# STM32H7_Expand.net
KiCad netlist of a schematic drawn in Altium Designer
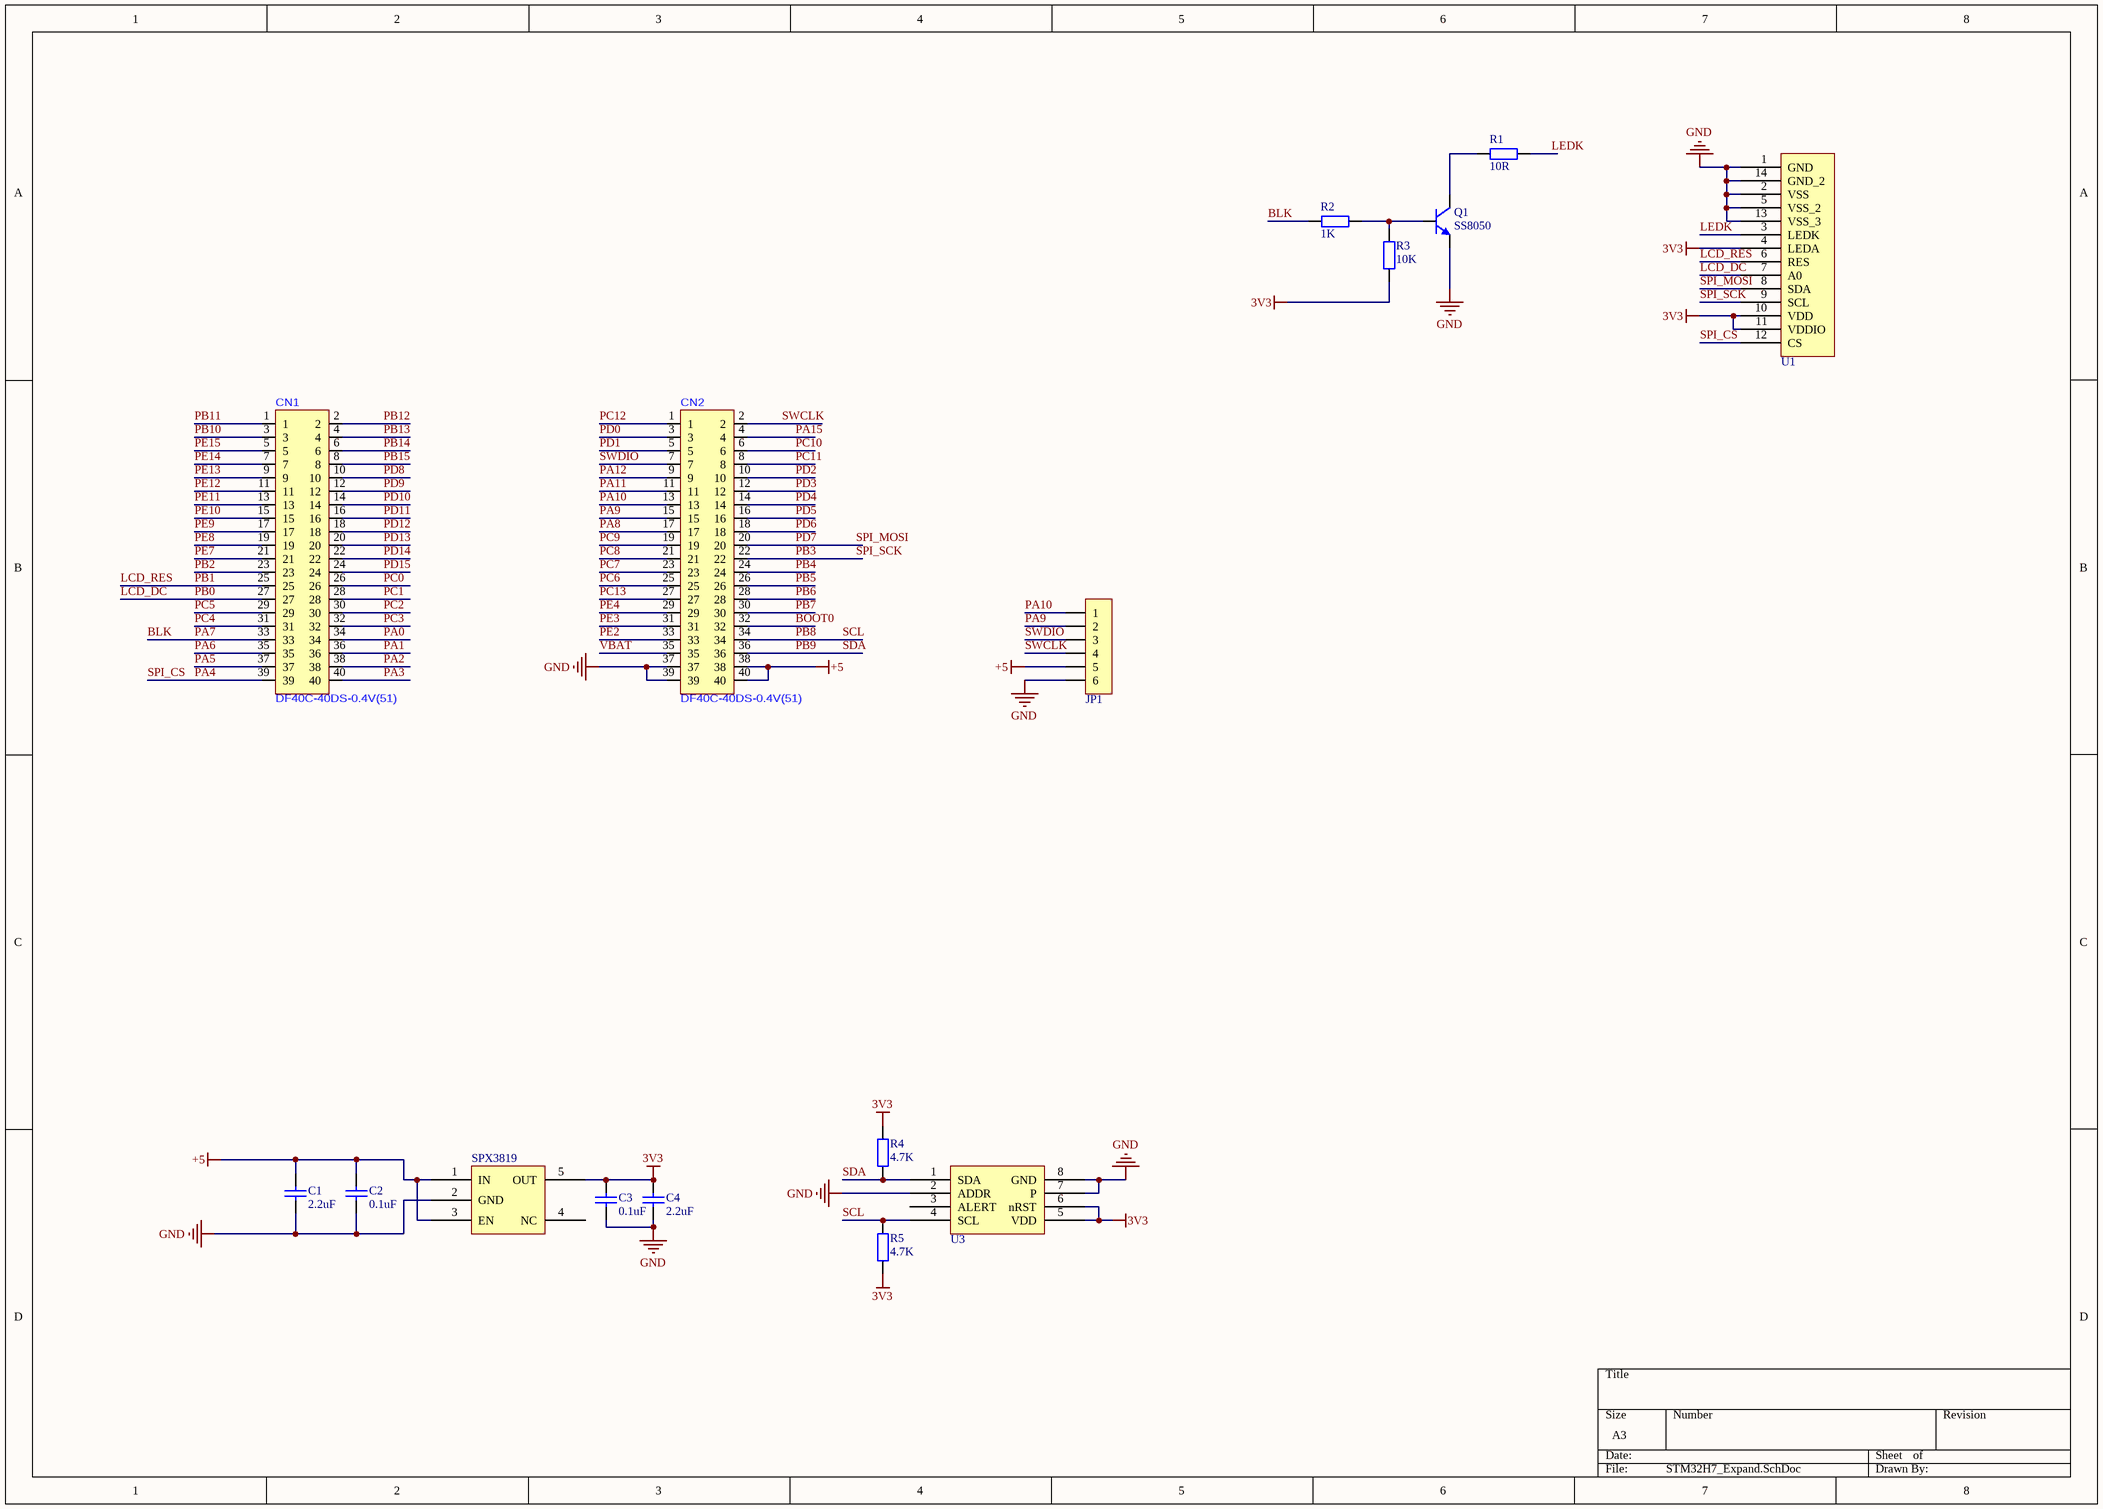
[diagram p0: STM32H7_Expand.SchDoc]

(export (version "E")
  (design (tool "Eeschema 10.0.6"))
  (components
    (comp (ref "C1")
      (value "2.2uF")
      (footprint "C0603_L")
      (description "贴片电容")
      (libsource (lib "0.1 - 电阻-电容-电感-电位器") (part "C"))
    )
    (comp (ref "C2")
      (value "0.1uF")
      (footprint "C0603_L")
      (description "贴片电容")
      (libsource (lib "0.1 - 电阻-电容-电感-电位器") (part "C"))
    )
    (comp (ref "C3")
      (value "0.1uF")
      (footprint "C0603_L")
      (description "贴片电容")
      (libsource (lib "0.1 - 电阻-电容-电感-电位器") (part "C"))
    )
    (comp (ref "C4")
      (value "2.2uF")
      (footprint "C0603_L")
      (description "贴片电容")
      (libsource (lib "0.1 - 电阻-电容-电感-电位器") (part "C"))
    )
    (comp (ref "CN1")
      (value "DF40C-40DS-0.4V(51)")
      (footprint "DF40C-40DS-0.4V")
      (description "BTB 母座\r\nC424644")
      (libsource (lib "Pi") (part "DF40C-40DS-0.4V(51)"))
    )
    (comp (ref "CN2")
      (value "DF40C-40DS-0.4V(51)")
      (footprint "DF40C-40DS-0.4V")
      (description "BTB 母座\r\nC424644")
      (libsource (lib "Pi") (part "DF40C-40DS-0.4V(51)"))
    )
    (comp (ref "JP1")
      (value "HDR-1X6")
      (footprint "ZH1.5-WS-6P")
      (description "6P接插件")
      (libsource (lib "5.2 - 接插件-脚距1.5") (part "Header 6"))
    )
    (comp (ref "Q1")
      (value "SS8050")
      (footprint "SOT23-3N")
      (description "C2150 \r\nNPN")
      (libsource (lib "0.4 - 三极管-场效应管-可控硅") (part "8050-SMD"))
    )
    (comp (ref "R1")
      (value "10R")
      (footprint "R0603_L")
      (description "贴片电阻")
      (libsource (lib "0.1 - 电阻-电容-电感-电位器") (part "R"))
    )
    (comp (ref "R2")
      (value "1K")
      (footprint "R0603_L")
      (description "贴片电阻")
      (libsource (lib "0.1 - 电阻-电容-电感-电位器") (part "R"))
    )
    (comp (ref "R3")
      (value "10K")
      (footprint "R0603_L")
      (description "贴片电阻")
      (libsource (lib "0.1 - 电阻-电容-电感-电位器") (part "R"))
    )
    (comp (ref "R4")
      (value "4.7K")
      (footprint "R0603_L")
      (description "贴片电阻")
      (libsource (lib "0.1 - 电阻-电容-电感-电位器") (part "R"))
    )
    (comp (ref "R5")
      (value "4.7K")
      (footprint "R0603_L")
      (description "贴片电阻")
      (libsource (lib "0.1 - 电阻-电容-电感-电位器") (part "R"))
    )
    (comp (ref "U1")
      (value "SPI144-14")
      (footprint "FPC-0.8-14PIN")
      (libsource (lib "Pi") (part "SPI144-14"))
    )
    (comp (ref "U2") (value "SPX3819") (footprint "SOT23-5L") (libsource (lib "Ball_PCB") (part "SPX3819")))
    (comp (ref "U3")
      (value "GXTS03")
      (footprint "DFN-8")
      (description "温度传感器\r\nC571219")
      (libsource (lib "Pi") (part "GXTS03"))
    )
  )
  (nets
    (net (code "1") (name "+5") (class "Default")
      (node (ref "C1") (pin "2") (pinfunction "2_2") (pintype "passive"))
      (node (ref "C2") (pin "2") (pinfunction "2_2") (pintype "passive"))
      (node (ref "CN2") (pin "38") (pinfunction "38_38") (pintype "passive"))
      (node (ref "CN2") (pin "40") (pinfunction "40_40") (pintype "passive"))
      (node (ref "JP1") (pin "5") (pinfunction "5_5") (pintype "passive"))
      (node (ref "U2") (pin "1") (pinfunction "IN_1") (pintype "passive"))
      (node (ref "U2") (pin "3") (pinfunction "EN_3") (pintype "passive"))
    )
    (net (code "2") (name "/BLK") (class "Default")
      (node (ref "CN1") (pin "33") (pinfunction "33_33") (pintype "passive"))
      (node (ref "R2") (pin "1") (pinfunction "1_1") (pintype "passive"))
    )
    (net (code "3") (name "/BOOT0") (class "Default")
      (node (ref "CN2") (pin "32") (pinfunction "32_32") (pintype "passive"))
    )
    (net (code "4") (name "/LCD_DC") (class "Default")
      (node (ref "CN1") (pin "27") (pinfunction "27_27") (pintype "passive"))
      (node (ref "U1") (pin "7") (pinfunction "A0_7") (pintype "passive"))
    )
    (net (code "5") (name "/LCD_RES") (class "Default")
      (node (ref "CN1") (pin "25") (pinfunction "25_25") (pintype "passive"))
      (node (ref "U1") (pin "6") (pinfunction "RES_6") (pintype "passive"))
    )
    (net (code "6") (name "/LEDK") (class "Default")
      (node (ref "R1") (pin "1") (pinfunction "1_1") (pintype "passive"))
      (node (ref "U1") (pin "3") (pinfunction "LEDK_3") (pintype "passive"))
    )
    (net (code "7") (name "/PA0") (class "Default")
      (node (ref "CN1") (pin "34") (pinfunction "34_34") (pintype "passive"))
    )
    (net (code "8") (name "/PA1") (class "Default")
      (node (ref "CN1") (pin "36") (pinfunction "36_36") (pintype "passive"))
    )
    (net (code "9") (name "/PA2") (class "Default")
      (node (ref "CN1") (pin "38") (pinfunction "38_38") (pintype "passive"))
    )
    (net (code "10") (name "/PA3") (class "Default")
      (node (ref "CN1") (pin "40") (pinfunction "40_40") (pintype "passive"))
    )
    (net (code "11") (name "/PA4") (class "Default")
      (node (ref "CN1") (pin "39") (pinfunction "39_39") (pintype "passive"))
      (node (ref "U1") (pin "12") (pinfunction "CS_12") (pintype "passive"))
    )
    (net (code "12") (name "/PA5") (class "Default")
      (node (ref "CN1") (pin "37") (pinfunction "37_37") (pintype "passive"))
    )
    (net (code "13") (name "/PA6") (class "Default")
      (node (ref "CN1") (pin "35") (pinfunction "35_35") (pintype "passive"))
    )
    (net (code "14") (name "/PA8") (class "Default")
      (node (ref "CN2") (pin "17") (pinfunction "17_17") (pintype "passive"))
    )
    (net (code "15") (name "/PA9") (class "Default")
      (node (ref "CN2") (pin "15") (pinfunction "15_15") (pintype "passive"))
      (node (ref "JP1") (pin "2") (pinfunction "2_2") (pintype "passive"))
    )
    (net (code "16") (name "/PA10") (class "Default")
      (node (ref "CN2") (pin "13") (pinfunction "13_13") (pintype "passive"))
      (node (ref "JP1") (pin "1") (pinfunction "1_1") (pintype "passive"))
    )
    (net (code "17") (name "/PA11") (class "Default")
      (node (ref "CN2") (pin "11") (pinfunction "11_11") (pintype "passive"))
    )
    (net (code "18") (name "/PA12") (class "Default")
      (node (ref "CN2") (pin "9") (pinfunction "9_9") (pintype "passive"))
    )
    (net (code "19") (name "/PA15") (class "Default")
      (node (ref "CN2") (pin "4") (pinfunction "4_4") (pintype "passive"))
    )
    (net (code "20") (name "/PB2") (class "Default")
      (node (ref "CN1") (pin "23") (pinfunction "23_23") (pintype "passive"))
    )
    (net (code "21") (name "/PB3") (class "Default")
      (node (ref "CN2") (pin "22") (pinfunction "22_22") (pintype "passive"))
      (node (ref "U1") (pin "9") (pinfunction "SCL_9") (pintype "passive"))
    )
    (net (code "22") (name "/PB4") (class "Default")
      (node (ref "CN2") (pin "24") (pinfunction "24_24") (pintype "passive"))
    )
    (net (code "23") (name "/PB5") (class "Default")
      (node (ref "CN2") (pin "26") (pinfunction "26_26") (pintype "passive"))
    )
    (net (code "24") (name "/PB6") (class "Default")
      (node (ref "CN2") (pin "28") (pinfunction "28_28") (pintype "passive"))
    )
    (net (code "25") (name "/PB7") (class "Default")
      (node (ref "CN2") (pin "30") (pinfunction "30_30") (pintype "passive"))
    )
    (net (code "26") (name "/PB8") (class "Default")
      (node (ref "CN2") (pin "34") (pinfunction "34_34") (pintype "passive"))
      (node (ref "R5") (pin "2") (pinfunction "2_2") (pintype "passive"))
      (node (ref "U3") (pin "4") (pinfunction "SCL_4") (pintype "passive"))
    )
    (net (code "27") (name "/PB9") (class "Default")
      (node (ref "CN2") (pin "36") (pinfunction "36_36") (pintype "passive"))
      (node (ref "R4") (pin "1") (pinfunction "1_1") (pintype "passive"))
      (node (ref "U3") (pin "1") (pinfunction "SDA_1") (pintype "passive"))
    )
    (net (code "28") (name "/PB10") (class "Default")
      (node (ref "CN1") (pin "3") (pinfunction "3_3") (pintype "passive"))
    )
    (net (code "29") (name "/PB11") (class "Default")
      (node (ref "CN1") (pin "1") (pinfunction "1_1") (pintype "passive"))
    )
    (net (code "30") (name "/PB12") (class "Default")
      (node (ref "CN1") (pin "2") (pinfunction "2_2") (pintype "passive"))
    )
    (net (code "31") (name "/PB13") (class "Default")
      (node (ref "CN1") (pin "4") (pinfunction "4_4") (pintype "passive"))
    )
    (net (code "32") (name "/PB14") (class "Default")
      (node (ref "CN1") (pin "6") (pinfunction "6_6") (pintype "passive"))
    )
    (net (code "33") (name "/PB15") (class "Default")
      (node (ref "CN1") (pin "8") (pinfunction "8_8") (pintype "passive"))
    )
    (net (code "34") (name "/PC0") (class "Default")
      (node (ref "CN1") (pin "26") (pinfunction "26_26") (pintype "passive"))
    )
    (net (code "35") (name "/PC1") (class "Default")
      (node (ref "CN1") (pin "28") (pinfunction "28_28") (pintype "passive"))
    )
    (net (code "36") (name "/PC2") (class "Default")
      (node (ref "CN1") (pin "30") (pinfunction "30_30") (pintype "passive"))
    )
    (net (code "37") (name "/PC3") (class "Default")
      (node (ref "CN1") (pin "32") (pinfunction "32_32") (pintype "passive"))
    )
    (net (code "38") (name "/PC4") (class "Default")
      (node (ref "CN1") (pin "31") (pinfunction "31_31") (pintype "passive"))
    )
    (net (code "39") (name "/PC5") (class "Default")
      (node (ref "CN1") (pin "29") (pinfunction "29_29") (pintype "passive"))
    )
    (net (code "40") (name "/PC6") (class "Default")
      (node (ref "CN2") (pin "25") (pinfunction "25_25") (pintype "passive"))
    )
    (net (code "41") (name "/PC7") (class "Default")
      (node (ref "CN2") (pin "23") (pinfunction "23_23") (pintype "passive"))
    )
    (net (code "42") (name "/PC8") (class "Default")
      (node (ref "CN2") (pin "21") (pinfunction "21_21") (pintype "passive"))
    )
    (net (code "43") (name "/PC9") (class "Default")
      (node (ref "CN2") (pin "19") (pinfunction "19_19") (pintype "passive"))
    )
    (net (code "44") (name "/PC10") (class "Default")
      (node (ref "CN2") (pin "6") (pinfunction "6_6") (pintype "passive"))
    )
    (net (code "45") (name "/PC11") (class "Default")
      (node (ref "CN2") (pin "8") (pinfunction "8_8") (pintype "passive"))
    )
    (net (code "46") (name "/PC12") (class "Default")
      (node (ref "CN2") (pin "1") (pinfunction "1_1") (pintype "passive"))
    )
    (net (code "47") (name "/PC13") (class "Default")
      (node (ref "CN2") (pin "27") (pinfunction "27_27") (pintype "passive"))
    )
    (net (code "48") (name "/PD0") (class "Default")
      (node (ref "CN2") (pin "3") (pinfunction "3_3") (pintype "passive"))
    )
    (net (code "49") (name "/PD1") (class "Default")
      (node (ref "CN2") (pin "5") (pinfunction "5_5") (pintype "passive"))
    )
    (net (code "50") (name "/PD2") (class "Default")
      (node (ref "CN2") (pin "10") (pinfunction "10_10") (pintype "passive"))
    )
    (net (code "51") (name "/PD3") (class "Default")
      (node (ref "CN2") (pin "12") (pinfunction "12_12") (pintype "passive"))
    )
    (net (code "52") (name "/PD4") (class "Default")
      (node (ref "CN2") (pin "14") (pinfunction "14_14") (pintype "passive"))
    )
    (net (code "53") (name "/PD5") (class "Default")
      (node (ref "CN2") (pin "16") (pinfunction "16_16") (pintype "passive"))
    )
    (net (code "54") (name "/PD6") (class "Default")
      (node (ref "CN2") (pin "18") (pinfunction "18_18") (pintype "passive"))
    )
    (net (code "55") (name "/PD7") (class "Default")
      (node (ref "CN2") (pin "20") (pinfunction "20_20") (pintype "passive"))
      (node (ref "U1") (pin "8") (pinfunction "SDA_8") (pintype "passive"))
    )
    (net (code "56") (name "/PD8") (class "Default")
      (node (ref "CN1") (pin "10") (pinfunction "10_10") (pintype "passive"))
    )
    (net (code "57") (name "/PD9") (class "Default")
      (node (ref "CN1") (pin "12") (pinfunction "12_12") (pintype "passive"))
    )
    (net (code "58") (name "/PD10") (class "Default")
      (node (ref "CN1") (pin "14") (pinfunction "14_14") (pintype "passive"))
    )
    (net (code "59") (name "/PD11") (class "Default")
      (node (ref "CN1") (pin "16") (pinfunction "16_16") (pintype "passive"))
    )
    (net (code "60") (name "/PD12") (class "Default")
      (node (ref "CN1") (pin "18") (pinfunction "18_18") (pintype "passive"))
    )
    (net (code "61") (name "/PD13") (class "Default")
      (node (ref "CN1") (pin "20") (pinfunction "20_20") (pintype "passive"))
    )
    (net (code "62") (name "/PD14") (class "Default")
      (node (ref "CN1") (pin "22") (pinfunction "22_22") (pintype "passive"))
    )
    (net (code "63") (name "/PD15") (class "Default")
      (node (ref "CN1") (pin "24") (pinfunction "24_24") (pintype "passive"))
    )
    (net (code "64") (name "/PE2") (class "Default")
      (node (ref "CN2") (pin "33") (pinfunction "33_33") (pintype "passive"))
    )
    (net (code "65") (name "/PE3") (class "Default")
      (node (ref "CN2") (pin "31") (pinfunction "31_31") (pintype "passive"))
    )
    (net (code "66") (name "/PE4") (class "Default")
      (node (ref "CN2") (pin "29") (pinfunction "29_29") (pintype "passive"))
    )
    (net (code "67") (name "/PE7") (class "Default")
      (node (ref "CN1") (pin "21") (pinfunction "21_21") (pintype "passive"))
    )
    (net (code "68") (name "/PE8") (class "Default")
      (node (ref "CN1") (pin "19") (pinfunction "19_19") (pintype "passive"))
    )
    (net (code "69") (name "/PE9") (class "Default")
      (node (ref "CN1") (pin "17") (pinfunction "17_17") (pintype "passive"))
    )
    (net (code "70") (name "/PE10") (class "Default")
      (node (ref "CN1") (pin "15") (pinfunction "15_15") (pintype "passive"))
    )
    (net (code "71") (name "/PE11") (class "Default")
      (node (ref "CN1") (pin "13") (pinfunction "13_13") (pintype "passive"))
    )
    (net (code "72") (name "/PE12") (class "Default")
      (node (ref "CN1") (pin "11") (pinfunction "11_11") (pintype "passive"))
    )
    (net (code "73") (name "/PE13") (class "Default")
      (node (ref "CN1") (pin "9") (pinfunction "9_9") (pintype "passive"))
    )
    (net (code "74") (name "/PE14") (class "Default")
      (node (ref "CN1") (pin "7") (pinfunction "7_7") (pintype "passive"))
    )
    (net (code "75") (name "/PE15") (class "Default")
      (node (ref "CN1") (pin "5") (pinfunction "5_5") (pintype "passive"))
    )
    (net (code "76") (name "/SWCLK") (class "Default")
      (node (ref "CN2") (pin "2") (pinfunction "2_2") (pintype "passive"))
      (node (ref "JP1") (pin "4") (pinfunction "4_4") (pintype "passive"))
    )
    (net (code "77") (name "/SWDIO") (class "Default")
      (node (ref "CN2") (pin "7") (pinfunction "7_7") (pintype "passive"))
      (node (ref "JP1") (pin "3") (pinfunction "3_3") (pintype "passive"))
    )
    (net (code "78") (name "/VBAT") (class "Default")
      (node (ref "CN2") (pin "35") (pinfunction "35_35") (pintype "passive"))
    )
    (net (code "79") (name "3V3") (class "Default")
      (node (ref "C3") (pin "2") (pinfunction "2_2") (pintype "passive"))
      (node (ref "C4") (pin "2") (pinfunction "2_2") (pintype "passive"))
      (node (ref "R3") (pin "1") (pinfunction "1_1") (pintype "passive"))
      (node (ref "R4") (pin "2") (pinfunction "2_2") (pintype "passive"))
      (node (ref "R5") (pin "1") (pinfunction "1_1") (pintype "passive"))
      (node (ref "U1") (pin "10") (pinfunction "VDD_10") (pintype "passive"))
      (node (ref "U1") (pin "11") (pinfunction "VDDIO_11") (pintype "passive"))
      (node (ref "U1") (pin "4") (pinfunction "LEDA_4") (pintype "passive"))
      (node (ref "U2") (pin "5") (pinfunction "OUT_5") (pintype "passive"))
      (node (ref "U3") (pin "5") (pinfunction "VDD_5") (pintype "passive"))
      (node (ref "U3") (pin "6") (pinfunction "nRST_6") (pintype "passive"))
    )
    (net (code "80") (name "GND") (class "Default")
      (node (ref "C1") (pin "1") (pinfunction "1_1") (pintype "passive"))
      (node (ref "C2") (pin "1") (pinfunction "1_1") (pintype "passive"))
      (node (ref "C3") (pin "1") (pinfunction "1_1") (pintype "passive"))
      (node (ref "C4") (pin "1") (pinfunction "1_1") (pintype "passive"))
      (node (ref "CN2") (pin "37") (pinfunction "37_37") (pintype "passive"))
      (node (ref "CN2") (pin "39") (pinfunction "39_39") (pintype "passive"))
      (node (ref "JP1") (pin "6") (pinfunction "6_6") (pintype "passive"))
      (node (ref "Q1") (pin "2") (pinfunction "E_2") (pintype "passive"))
      (node (ref "U1") (pin "1") (pinfunction "GND_1") (pintype "passive"))
      (node (ref "U1") (pin "13") (pinfunction "VSS_3_13") (pintype "passive"))
      (node (ref "U1") (pin "14") (pinfunction "GND_2_14") (pintype "passive"))
      (node (ref "U1") (pin "2") (pinfunction "VSS_2") (pintype "passive"))
      (node (ref "U1") (pin "5") (pinfunction "VSS_2_5") (pintype "passive"))
      (node (ref "U2") (pin "2") (pinfunction "GND_2") (pintype "passive"))
      (node (ref "U3") (pin "2") (pinfunction "ADDR_2") (pintype "passive"))
      (node (ref "U3") (pin "7") (pinfunction "P_7") (pintype "passive"))
      (node (ref "U3") (pin "8") (pinfunction "GND_8") (pintype "passive"))
    )
    (net (code "81") (name "Net-(Q1-B)") (class "Default")
      (node (ref "Q1") (pin "1") (pinfunction "B_1") (pintype "passive"))
      (node (ref "R2") (pin "2") (pinfunction "2_2") (pintype "passive"))
      (node (ref "R3") (pin "2") (pinfunction "2_2") (pintype "passive"))
    )
    (net (code "82") (name "Net-(Q1-C)") (class "Default")
      (node (ref "Q1") (pin "3") (pinfunction "C_3") (pintype "passive"))
      (node (ref "R1") (pin "2") (pinfunction "2_2") (pintype "passive"))
    )
    (net (code "83") (name "unconnected-(U2-NC-Pad4)") (class "Default")
      (node (ref "U2") (pin "4") (pinfunction "NC_4") (pintype "passive"))
    )
    (net (code "84") (name "unconnected-(U3-ALERT-Pad3)") (class "Default")
      (node (ref "U3") (pin "3") (pinfunction "ALERT_3") (pintype "passive"))
    )
  )
)
